# Power_supply.net
KiCad netlist of a schematic drawn in Altium Designer
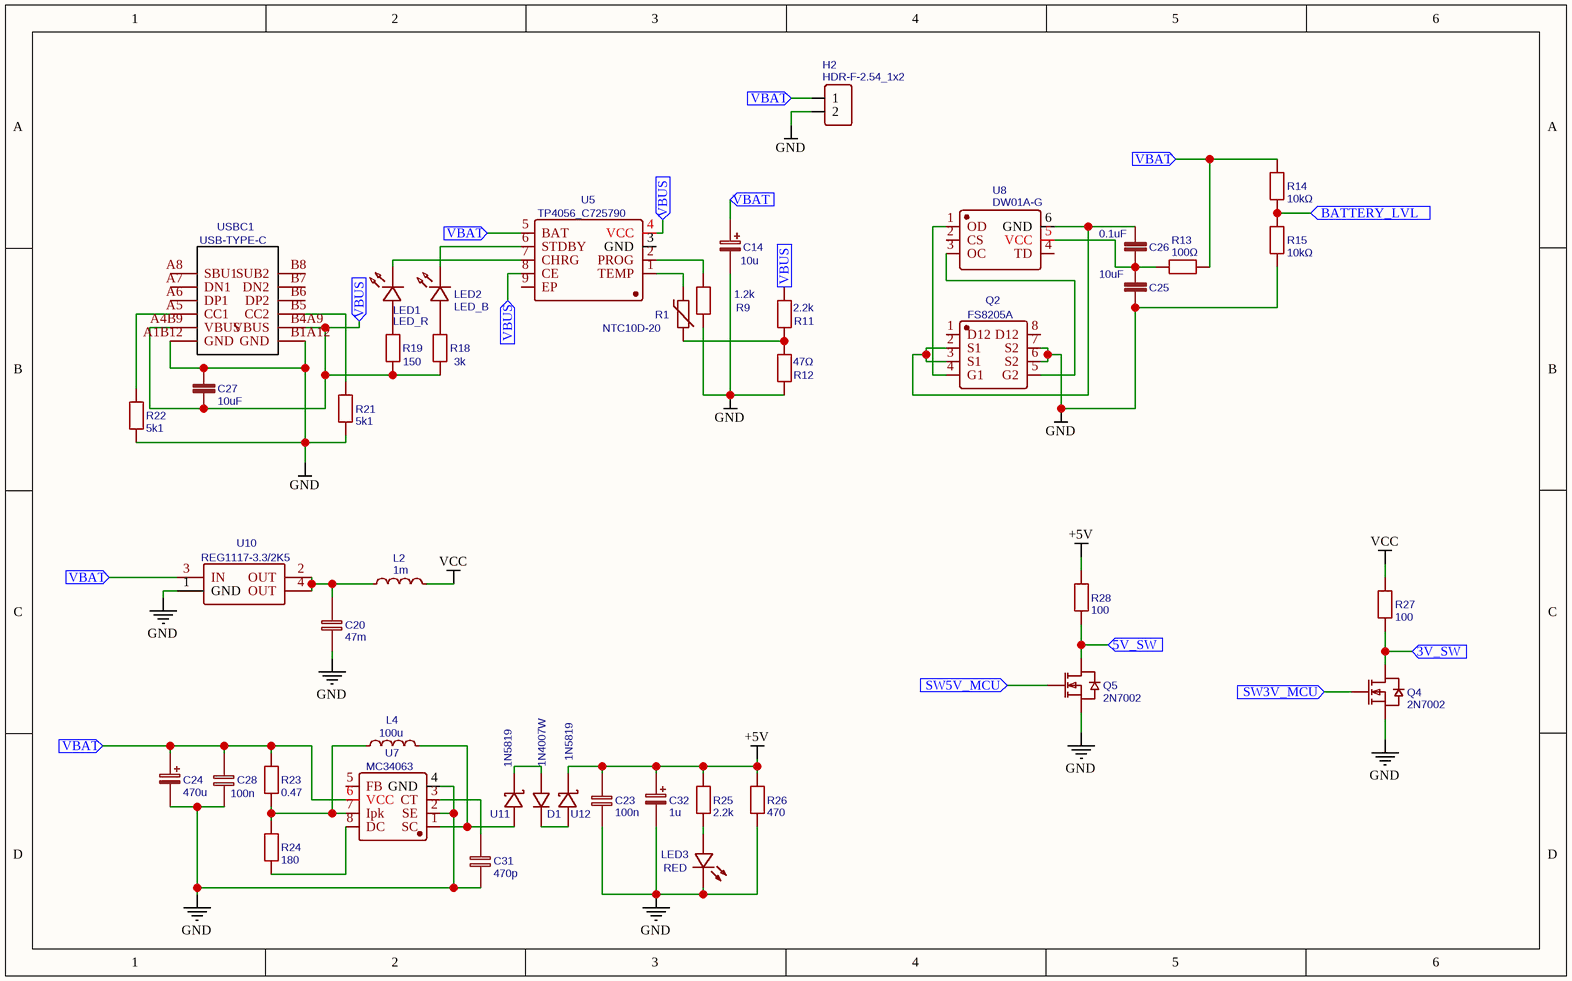
[diagram p0: Power supply.schdoc]

(export (version "E")
  (design (tool "Eeschema 10.0.6"))
  (components
    (comp (ref "C20")
      (value "47m")
      (fields (field (name "CONTRIBUTOR") "LCEDA_Lib"))
      (libsource (lib "altium-import") (part "root_1_47m_"))
    )
    (comp (ref "C23")
      (value "100n")
      (fields (field (name "CONTRIBUTOR") "LCEDA_Lib"))
      (libsource (lib "altium-import") (part "root_1_100n_"))
    )
    (comp (ref "C24")
      (value "470u")
      (fields (field (name "CONTRIBUTOR") "LCEDA_Lib"))
      (libsource (lib "altium-import") (part "root_3_470u_"))
    )
    (comp (ref "C25")
      (value "10uF")
      (description "CAP-00810")
      (fields (field (name "CONTRIBUTOR") "SparkFun"))
      (libsource (lib "altium-import") (part "root_0_10uF_"))
    )
    (comp (ref "C26")
      (value "0.1uF")
      (description "CAP-00810")
      (fields (field (name "CONTRIBUTOR") "SparkFun"))
      (libsource (lib "altium-import") (part "root_0_0.1uF_"))
    )
    (comp (ref "C27")
      (value "10uF")
      (description "CAP-00810")
      (fields (field (name "CONTRIBUTOR") "SparkFun"))
      (libsource (lib "altium-import") (part "root_2_10uF_"))
    )
    (comp (ref "C28")
      (value "100n")
      (fields (field (name "CONTRIBUTOR") "LCEDA_Lib"))
      (libsource (lib "altium-import") (part "root_1_100n_"))
    )
    (comp (ref "C31")
      (value "470p")
      (fields (field (name "CONTRIBUTOR") "LCEDA_Lib"))
      (libsource (lib "altium-import") (part "root_1_470p_"))
    )
    (comp (ref "C32")
      (value "1u")
      (fields (field (name "CONTRIBUTOR") "LCEDA_Lib"))
      (libsource (lib "altium-import") (part "root_3_1u_"))
    )
    (comp (ref "D1")
      (value "1N4007W")
      (fields (field (name "BOM_SUPPLIER PART") "C328592") (field (name "CONTRIBUTOR") "LCEDA_Lib"))
      (libsource (lib "altium-import") (part "root_3_1N4007W_"))
    )
    (comp (ref "H2")
      (value "HDR-F-2.54_1x2")
      (fields (field (name "BOM_SUPPLIER PART") "C49661") (field (name "CONTRIBUTOR") "LCEDA_Lib"))
      (libsource (lib "altium-import") (part "root_0_HDR-F-2.54_1x2_"))
    )
    (comp (ref "L2")
      (value "1m")
      (fields (field (name "CONTRIBUTOR") "LCEDA_Lib"))
      (libsource (lib "altium-import") (part "root_0_1m_"))
    )
    (comp (ref "L4")
      (value "100u")
      (fields (field (name "CONTRIBUTOR") "LCEDA_Lib"))
      (libsource (lib "altium-import") (part "root_0_100u_"))
    )
    (comp (ref "LED1")
      (value "LED_R")
      (fields
        (field (name "BOM_MANUFACTURER PART") "19-217/R6C-AL1M2VY/3T")
        (field (name "BOM_SUPPLIER PART") "C72044")
        (field (name "CONTRIBUTOR") "LCEDA_01")
      )
      (libsource (lib "altium-import") (part "root_1_LED_R_"))
    )
    (comp (ref "LED2")
      (value "LED_B")
      (fields
        (field (name "BOM_MANUFACTURER PART") "19-217/BHC-ZL1M2RY/3T")
        (field (name "BOM_SUPPLIER PART") "C72041")
        (field (name "CONTRIBUTOR") "LCEDA_01")
      )
      (libsource (lib "altium-import") (part "root_1_LED_B_"))
    )
    (comp (ref "LED3")
      (value "RED")
      (fields
        (field (name "BOM_MANUFACTURER PART") "whiteLEDSMD")
        (field (name "BOM_SUPPLIER PART") "C34499")
      )
      (libsource (lib "altium-import") (part "root_3_RED_"))
    )
    (comp (ref "Q2")
      (value "FS8205A")
      (fields (field (name "BOM_SUPPLIER PART") "C16052"))
      (libsource (lib "altium-import") (part "root_0_FS8205A_"))
    )
    (comp (ref "Q4")
      (value "2N7002")
      (fields
        (field (name "BOM_MANUFACTURER PART") "2N7002,215")
        (field (name "BOM_SUPPLIER PART") "C65189")
        (field (name "CONTRIBUTOR") "LCEDA_Lib")
      )
      (libsource (lib "altium-import") (part "root_0_2N7002_"))
    )
    (comp (ref "Q5")
      (value "2N7002")
      (fields
        (field (name "BOM_MANUFACTURER PART") "2N7002,215")
        (field (name "BOM_SUPPLIER PART") "C65189")
        (field (name "CONTRIBUTOR") "LCEDA_Lib")
      )
      (libsource (lib "altium-import") (part "root_0_2N7002_"))
    )
    (comp (ref "R1")
      (value "NTC10D-20")
      (fields
        (field (name "BOM_MANUFACTURER PART") "NTCThermistor")
        (field (name "BOM_SUPPLIER PART") "C42975")
        (field (name "CONTRIBUTOR") "wm_irsyaduddin")
      )
      (libsource (lib "altium-import") (part "root_3_NTC10D-20_"))
    )
    (comp (ref "R9")
      (value "1.2k")
      (fields
        (field (name "BOM_SUPPLIER PART") "C525388")
        (field (name "BOM_MANUFACTURER PART") "TCTR0603F47K0F3960T")
        (field (name "CONTRIBUTOR") "LCSC")
      )
      (libsource (lib "altium-import") (part "root_1_1.2k_"))
    )
    (comp (ref "R11")
      (value "2.2k")
      (fields
        (field (name "BOM_SUPPLIER PART") "C525388")
        (field (name "BOM_MANUFACTURER PART") "TCTR0603F47K0F3960T")
        (field (name "CONTRIBUTOR") "LCSC")
      )
      (libsource (lib "altium-import") (part "root_1_2.2k_"))
    )
    (comp (ref "R12")
      (value "47Ω")
      (fields
        (field (name "BOM_SUPPLIER PART") "C525388")
        (field (name "BOM_MANUFACTURER PART") "TCTR0603F47K0F3960T")
        (field (name "CONTRIBUTOR") "LCSC")
      )
      (libsource (lib "altium-import") (part "root_1_47Ω_"))
    )
    (comp (ref "R13")
      (value "100Ω")
      (fields
        (field (name "BOM_SUPPLIER PART") "C525388")
        (field (name "BOM_MANUFACTURER PART") "TCTR0603F47K0F3960T")
        (field (name "CONTRIBUTOR") "LCSC")
      )
      (libsource (lib "altium-import") (part "root_2_100Ω_"))
    )
    (comp (ref "R14")
      (value "10kΩ")
      (fields
        (field (name "BOM_SUPPLIER PART") "C525388")
        (field (name "BOM_MANUFACTURER PART") "TCTR0603F47K0F3960T")
        (field (name "CONTRIBUTOR") "LCSC")
      )
      (libsource (lib "altium-import") (part "root_3_10kΩ_"))
    )
    (comp (ref "R15")
      (value "10kΩ")
      (fields
        (field (name "BOM_SUPPLIER PART") "C525388")
        (field (name "BOM_MANUFACTURER PART") "TCTR0603F47K0F3960T")
        (field (name "CONTRIBUTOR") "LCSC")
      )
      (libsource (lib "altium-import") (part "root_3_10kΩ_"))
    )
    (comp (ref "R18")
      (value "3k")
      (fields
        (field (name "BOM_SUPPLIER PART") "C525388")
        (field (name "BOM_MANUFACTURER PART") "TCTR0603F47K0F3960T")
        (field (name "CONTRIBUTOR") "LCSC")
      )
      (libsource (lib "altium-import") (part "root_1_3k_"))
    )
    (comp (ref "R19")
      (value "150")
      (fields
        (field (name "BOM_SUPPLIER PART") "C525388")
        (field (name "BOM_MANUFACTURER PART") "TCTR0603F47K0F3960T")
        (field (name "CONTRIBUTOR") "LCSC")
      )
      (libsource (lib "altium-import") (part "root_1_150_"))
    )
    (comp (ref "R21")
      (value "5k1")
      (fields (field (name "CONTRIBUTOR") "LCEDA_Lib"))
      (libsource (lib "altium-import") (part "root_1_5k1_"))
    )
    (comp (ref "R22")
      (value "5k1")
      (fields (field (name "CONTRIBUTOR") "LCEDA_Lib"))
      (libsource (lib "altium-import") (part "root_1_5k1_"))
    )
    (comp (ref "R23")
      (value "0.47")
      (fields (field (name "CONTRIBUTOR") "LCEDA_Lib"))
      (libsource (lib "altium-import") (part "root_1_0.47_"))
    )
    (comp (ref "R24")
      (value "180")
      (fields (field (name "CONTRIBUTOR") "LCEDA_Lib"))
      (libsource (lib "altium-import") (part "root_1_180_"))
    )
    (comp (ref "R25")
      (value "2.2k")
      (fields (field (name "CONTRIBUTOR") "LCEDA_Lib"))
      (libsource (lib "altium-import") (part "root_1_2.2k_"))
    )
    (comp (ref "R26")
      (value "470")
      (fields (field (name "CONTRIBUTOR") "LCEDA_Lib"))
      (libsource (lib "altium-import") (part "root_1_470_"))
    )
    (comp (ref "R27")
      (value "100")
      (fields (field (name "CONTRIBUTOR") "LCEDA_Lib"))
      (libsource (lib "altium-import") (part "root_1_100_"))
    )
    (comp (ref "R28")
      (value "100")
      (fields (field (name "CONTRIBUTOR") "LCEDA_Lib"))
      (libsource (lib "altium-import") (part "root_1_100_"))
    )
    (comp (ref "U5")
      (value "TP4056_C725790")
      (fields
        (field (name "BOM_SUPPLIER PART") "C725790")
        (field (name "BOM_MANUFACTURER PART") "TP4056")
        (field (name "CONTRIBUTOR") "LCSC")
      )
      (libsource (lib "altium-import") (part "root_2_TP4056_C725790_"))
    )
    (comp (ref "U6")
      (value "electrolitic_cap_th_to_smd")
      (fields (field (name "CONTRIBUTOR") "c3xp"))
      (libsource (lib "altium-import") (part "root_3_electrolitic_cap_th_to_smd_"))
    )
    (comp (ref "U7")
      (value "MC34063")
      (fields
        (field (name "BOM_SUPPLIER PART") "C3014308")
        (field (name "BOM_MANUFACTURER PART") "MC34063ADR")
        (field (name "CONTRIBUTOR") "lcsc")
      )
      (libsource (lib "altium-import") (part "root_2_MC34063_"))
    )
    (comp (ref "U8")
      (value "DW01A-G")
      (fields (field (name "BOM_SUPPLIER PART") "C61503") (field (name "CONTRIBUTOR") "LCSC"))
      (libsource (lib "altium-import") (part "root_0_DW01A-G_"))
    )
    (comp (ref "U10")
      (value "REG1117-3.3/2K5")
      (fields (field (name "BOM_SUPPLIER PART") "C139396") (field (name "CONTRIBUTOR") "LCSC"))
      (libsource (lib "altium-import") (part "root_0_REG1117-3.3/2K5_"))
    )
    (comp (ref "U11")
      (value "1N5819")
      (fields (field (name "BOM_SUPPLIER PART") "C3039965") (field (name "CONTRIBUTOR") "lcsc"))
      (libsource (lib "altium-import") (part "root_3_1N5819_"))
    )
    (comp (ref "U12")
      (value "1N5819")
      (fields (field (name "BOM_SUPPLIER PART") "C3039965") (field (name "CONTRIBUTOR") "lcsc"))
      (libsource (lib "altium-import") (part "root_3_1N5819_"))
    )
    (comp (ref "USBC1")
      (value "USB-TYPE-C")
      (fields
        (field (name "BOM_SUPPLIER PART") "C223907")
        (field (name "BOM_MANUFACTURER PART") "TYPE-C-31-M-14")
        (field (name "CONTRIBUTOR") "Dragomir Liviu Marian")
      )
      (libsource (lib "altium-import") (part "root_0_USB-TYPE-C_"))
    )
  )
  (nets
    (net (code "1") (name "+5V") (class "Default")
      (node (ref "C23") (pin "2") (pinfunction "2_2") (pintype "passive"))
      (node (ref "C32") (pin "1") (pinfunction "1_1") (pintype "passive"))
      (node (ref "R25") (pin "2") (pinfunction "2_2") (pintype "passive"))
      (node (ref "R26") (pin "2") (pinfunction "2_2") (pintype "passive"))
      (node (ref "R28") (pin "2") (pinfunction "2_2") (pintype "passive"))
      (node (ref "U12") (pin "1") (pinfunction "K_1") (pintype "passive"))
    )
    (net (code "2") (name "/3V_SW") (class "Default")
      (node (ref "Q4") (pin "3") (pinfunction "D_3") (pintype "passive"))
      (node (ref "R27") (pin "1") (pinfunction "1_1") (pintype "passive"))
    )
    (net (code "3") (name "/5V_SW") (class "Default")
      (node (ref "Q5") (pin "3") (pinfunction "D_3") (pintype "passive"))
      (node (ref "R28") (pin "1") (pinfunction "1_1") (pintype "passive"))
    )
    (net (code "4") (name "/BATTERY_LVL") (class "Default")
      (node (ref "R14") (pin "2") (pinfunction "2_2") (pintype "passive"))
      (node (ref "R15") (pin "1") (pinfunction "1_1") (pintype "passive"))
    )
    (net (code "5") (name "/SW3V_MCU") (class "Default")
      (node (ref "Q4") (pin "1") (pinfunction "G_1") (pintype "passive"))
    )
    (net (code "6") (name "/SW5V_MCU") (class "Default")
      (node (ref "Q5") (pin "1") (pinfunction "G_1") (pintype "passive"))
    )
    (net (code "7") (name "/VBAT") (class "Default")
      (node (ref "C24") (pin "1") (pinfunction "1_1") (pintype "passive"))
      (node (ref "C28") (pin "2") (pinfunction "2_2") (pintype "passive"))
      (node (ref "H2") (pin "1") (pinfunction "1_1") (pintype "passive"))
      (node (ref "R13") (pin "1") (pinfunction "1_1") (pintype "passive"))
      (node (ref "R14") (pin "1") (pinfunction "1_1") (pintype "passive"))
      (node (ref "R23") (pin "2") (pinfunction "2_2") (pintype "passive"))
      (node (ref "U10") (pin "3") (pinfunction "IN_3") (pintype "passive"))
      (node (ref "U5") (pin "5") (pinfunction "BAT_5") (pintype "passive"))
      (node (ref "U6") (pin "1") (pinfunction "1_1") (pintype "passive"))
      (node (ref "U7") (pin "6") (pinfunction "VCC_6") (pintype "passive"))
    )
    (net (code "8") (name "/VBUS") (class "Default")
      (node (ref "C27") (pin "1") (pinfunction "1_1") (pintype "passive"))
      (node (ref "R11") (pin "2") (pinfunction "2_2") (pintype "passive"))
      (node (ref "R18") (pin "1") (pinfunction "1_1") (pintype "passive"))
      (node (ref "R19") (pin "1") (pinfunction "1_1") (pintype "passive"))
      (node (ref "U5") (pin "4") (pinfunction "VCC_4") (pintype "passive"))
      (node (ref "U5") (pin "8") (pinfunction "CE_8") (pintype "passive"))
      (node (ref "USBC1") (pin "A4B9") (pinfunction "VBUS_A4B9") (pintype "passive"))
      (node (ref "USBC1") (pin "B4A9") (pinfunction "VBUS_B4A9") (pintype "passive"))
    )
    (net (code "9") (name "GND") (class "Default")
      (node (ref "C20") (pin "1") (pinfunction "1_1") (pintype "passive"))
      (node (ref "C23") (pin "1") (pinfunction "1_1") (pintype "passive"))
      (node (ref "C24") (pin "2") (pinfunction "2_2") (pintype "passive"))
      (node (ref "C25") (pin "2") (pinfunction "2_2") (pintype "passive"))
      (node (ref "C27") (pin "2") (pinfunction "2_2") (pintype "passive"))
      (node (ref "C28") (pin "1") (pinfunction "1_1") (pintype "passive"))
      (node (ref "C31") (pin "1") (pinfunction "1_1") (pintype "passive"))
      (node (ref "C32") (pin "2") (pinfunction "2_2") (pintype "passive"))
      (node (ref "H2") (pin "2") (pinfunction "2_2") (pintype "passive"))
      (node (ref "LED3") (pin "2") (pinfunction "K_2") (pintype "passive"))
      (node (ref "Q2") (pin "6") (pinfunction "S2_6") (pintype "passive"))
      (node (ref "Q2") (pin "7") (pinfunction "S2_7") (pintype "passive"))
      (node (ref "Q4") (pin "2") (pinfunction "S_2") (pintype "passive"))
      (node (ref "Q5") (pin "2") (pinfunction "S_2") (pintype "passive"))
      (node (ref "R12") (pin "1") (pinfunction "1_1") (pintype "passive"))
      (node (ref "R15") (pin "2") (pinfunction "2_2") (pintype "passive"))
      (node (ref "R21") (pin "1") (pinfunction "1_1") (pintype "passive"))
      (node (ref "R22") (pin "1") (pinfunction "1_1") (pintype "passive"))
      (node (ref "R26") (pin "1") (pinfunction "1_1") (pintype "passive"))
      (node (ref "R9") (pin "1") (pinfunction "1_1") (pintype "passive"))
      (node (ref "U10") (pin "1") (pinfunction "GND_1") (pintype "passive"))
      (node (ref "U6") (pin "2") (pinfunction "2_2") (pintype "passive"))
      (node (ref "U7") (pin "2") (pinfunction "SE_2") (pintype "passive"))
      (node (ref "U7") (pin "4") (pinfunction "GND_4") (pintype "passive"))
      (node (ref "USBC1") (pin "A1B12") (pinfunction "GND_A1B12") (pintype "passive"))
      (node (ref "USBC1") (pin "B1A12") (pinfunction "GND_B1A12") (pintype "passive"))
    )
    (net (code "10") (name "Net-(C20-Pad2)") (class "Default")
      (node (ref "C20") (pin "2") (pinfunction "2_2") (pintype "passive"))
      (node (ref "L2") (pin "1") (pinfunction "1_1") (pintype "passive"))
      (node (ref "U10") (pin "2") (pinfunction "OUT_2") (pintype "passive"))
      (node (ref "U10") (pin "4") (pinfunction "OUT_4") (pintype "passive"))
    )
    (net (code "11") (name "Net-(LED1-Pad1)") (class "Default")
      (node (ref "LED1") (pin "1") (pinfunction "1_1") (pintype "passive"))
      (node (ref "R19") (pin "2") (pinfunction "2_2") (pintype "passive"))
    )
    (net (code "12") (name "Net-(LED2-Pad1)") (class "Default")
      (node (ref "LED2") (pin "1") (pinfunction "1_1") (pintype "passive"))
      (node (ref "R18") (pin "2") (pinfunction "2_2") (pintype "passive"))
    )
    (net (code "13") (name "Net-(LED3-A)") (class "Default")
      (node (ref "LED3") (pin "1") (pinfunction "A_1") (pintype "passive"))
      (node (ref "R25") (pin "1") (pinfunction "1_1") (pintype "passive"))
    )
    (net (code "14") (name "Net-(Q2-G1)") (class "Default")
      (node (ref "Q2") (pin "4") (pinfunction "G1_4") (pintype "passive"))
      (node (ref "U8") (pin "1") (pinfunction "OD_1") (pintype "passive"))
    )
    (net (code "15") (name "Net-(Q2-G2)") (class "Default")
      (node (ref "Q2") (pin "5") (pinfunction "G2_5") (pintype "passive"))
      (node (ref "U8") (pin "3") (pinfunction "OC_3") (pintype "passive"))
    )
    (net (code "16") (name "Net-(R1-Pad2)") (class "Default")
      (node (ref "R1") (pin "2") (pinfunction "2_2") (pintype "passive"))
      (node (ref "R11") (pin "1") (pinfunction "1_1") (pintype "passive"))
      (node (ref "R12") (pin "2") (pinfunction "2_2") (pintype "passive"))
    )
    (net (code "17") (name "Net-(U5-CHRG)") (class "Default")
      (node (ref "LED1") (pin "2") (pinfunction "2_2") (pintype "passive"))
      (node (ref "U5") (pin "7") (pinfunction "CHRG_7") (pintype "passive"))
    )
    (net (code "18") (name "Net-(U5-PROG)") (class "Default")
      (node (ref "R9") (pin "2") (pinfunction "2_2") (pintype "passive"))
      (node (ref "U5") (pin "2") (pinfunction "PROG_2") (pintype "passive"))
    )
    (net (code "19") (name "Net-(U5-STDBY)") (class "Default")
      (node (ref "LED2") (pin "2") (pinfunction "2_2") (pintype "passive"))
      (node (ref "U5") (pin "6") (pinfunction "STDBY_6") (pintype "passive"))
    )
    (net (code "20") (name "Net-(U5-TEMP)") (class "Default")
      (node (ref "R1") (pin "1") (pinfunction "1_1") (pintype "passive"))
      (node (ref "U5") (pin "1") (pinfunction "TEMP_1") (pintype "passive"))
    )
    (net (code "21") (name "Net-(U7-CT)") (class "Default")
      (node (ref "C31") (pin "2") (pinfunction "2_2") (pintype "passive"))
      (node (ref "U7") (pin "3") (pinfunction "CT_3") (pintype "passive"))
    )
    (net (code "22") (name "Net-(U7-DC)") (class "Default")
      (node (ref "R24") (pin "1") (pinfunction "1_1") (pintype "passive"))
      (node (ref "U7") (pin "8") (pinfunction "DC_8") (pintype "passive"))
    )
    (net (code "23") (name "Net-(U7-Ipk)") (class "Default")
      (node (ref "L4") (pin "1") (pinfunction "1_1") (pintype "passive"))
      (node (ref "R23") (pin "1") (pinfunction "1_1") (pintype "passive"))
      (node (ref "R24") (pin "2") (pinfunction "2_2") (pintype "passive"))
      (node (ref "U7") (pin "7") (pinfunction "Ipk_7") (pintype "passive"))
    )
    (net (code "24") (name "Net-(U8-GND)") (class "Default")
      (node (ref "C26") (pin "1") (pinfunction "1_1") (pintype "passive"))
      (node (ref "Q2") (pin "2") (pinfunction "S1_2") (pintype "passive"))
      (node (ref "Q2") (pin "3") (pinfunction "S1_3") (pintype "passive"))
      (node (ref "U8") (pin "6") (pinfunction "GND_6") (pintype "passive"))
    )
    (net (code "25") (name "Net-(U8-VCC)") (class "Default")
      (node (ref "C25") (pin "1") (pinfunction "1_1") (pintype "passive"))
      (node (ref "C26") (pin "2") (pinfunction "2_2") (pintype "passive"))
      (node (ref "R13") (pin "2") (pinfunction "2_2") (pintype "passive"))
      (node (ref "U8") (pin "5") (pinfunction "VCC_5") (pintype "passive"))
    )
    (net (code "26") (name "Net-(U11-A)") (class "Default")
      (node (ref "L4") (pin "2") (pinfunction "2_2") (pintype "passive"))
      (node (ref "U11") (pin "2") (pinfunction "A_2") (pintype "passive"))
      (node (ref "U7") (pin "1") (pinfunction "SC_1") (pintype "passive"))
    )
    (net (code "27") (name "Net-(U11-K)") (class "Default")
      (node (ref "D1") (pin "2") (pinfunction "2_2") (pintype "passive"))
      (node (ref "U11") (pin "1") (pinfunction "K_1") (pintype "passive"))
    )
    (net (code "28") (name "Net-(U12-A)") (class "Default")
      (node (ref "D1") (pin "1") (pinfunction "1_1") (pintype "passive"))
      (node (ref "U12") (pin "2") (pinfunction "A_2") (pintype "passive"))
    )
    (net (code "29") (name "Net-(USBC1-CC1)") (class "Default")
      (node (ref "R22") (pin "2") (pinfunction "2_2") (pintype "passive"))
      (node (ref "USBC1") (pin "A5") (pinfunction "CC1_A5") (pintype "passive"))
    )
    (net (code "30") (name "Net-(USBC1-CC2)") (class "Default")
      (node (ref "R21") (pin "2") (pinfunction "2_2") (pintype "passive"))
      (node (ref "USBC1") (pin "B5") (pinfunction "CC2_B5") (pintype "passive"))
    )
    (net (code "31") (name "VCC") (class "Default")
      (node (ref "L2") (pin "2") (pinfunction "2_2") (pintype "passive"))
      (node (ref "R27") (pin "2") (pinfunction "2_2") (pintype "passive"))
    )
    (net (code "32") (name "unconnected-(Q2-D12-Pad1)") (class "Default")
      (node (ref "Q2") (pin "1") (pinfunction "D12_1") (pintype "passive"))
    )
    (net (code "33") (name "unconnected-(Q2-D12-Pad8)") (class "Default")
      (node (ref "Q2") (pin "8") (pinfunction "D12_8") (pintype "passive"))
    )
    (net (code "34") (name "unconnected-(U5-EP-Pad9)") (class "Default")
      (node (ref "U5") (pin "9") (pinfunction "EP_9") (pintype "passive"))
    )
    (net (code "35") (name "unconnected-(U5-GND-Pad3)") (class "Default")
      (node (ref "U5") (pin "3") (pinfunction "GND_3") (pintype "passive"))
    )
    (net (code "36") (name "unconnected-(U7-FB-Pad5)") (class "Default")
      (node (ref "U7") (pin "5") (pinfunction "FB_5") (pintype "passive"))
    )
    (net (code "37") (name "unconnected-(U8-CS-Pad2)") (class "Default")
      (node (ref "U8") (pin "2") (pinfunction "CS_2") (pintype "passive"))
    )
    (net (code "38") (name "unconnected-(U8-TD-Pad4)") (class "Default")
      (node (ref "U8") (pin "4") (pinfunction "TD_4") (pintype "passive"))
    )
    (net (code "39") (name "unconnected-(USBC1-DN1-PadA7)") (class "Default")
      (node (ref "USBC1") (pin "A7") (pinfunction "DN1_A7") (pintype "passive"))
    )
    (net (code "40") (name "unconnected-(USBC1-DN2-PadB7)") (class "Default")
      (node (ref "USBC1") (pin "B7") (pinfunction "DN2_B7") (pintype "passive"))
    )
    (net (code "41") (name "unconnected-(USBC1-DP1-PadA6)") (class "Default")
      (node (ref "USBC1") (pin "A6") (pinfunction "DP1_A6") (pintype "passive"))
    )
    (net (code "42") (name "unconnected-(USBC1-DP2-PadB6)") (class "Default")
      (node (ref "USBC1") (pin "B6") (pinfunction "DP2_B6") (pintype "passive"))
    )
    (net (code "43") (name "unconnected-(USBC1-SBU1-PadA8)") (class "Default")
      (node (ref "USBC1") (pin "A8") (pinfunction "SBU1_A8") (pintype "passive"))
    )
    (net (code "44") (name "unconnected-(USBC1-SUB2-PadB8)") (class "Default")
      (node (ref "USBC1") (pin "B8") (pinfunction "SUB2_B8") (pintype "passive"))
    )
  )
)
